# design.net
KiCad netlist of a schematic drawn in Altium Designer
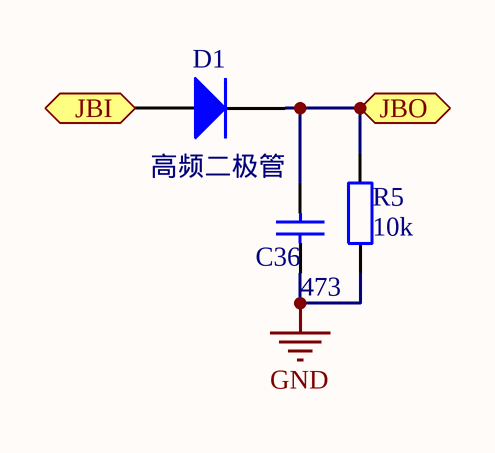
[diagram p0: 峰值检波.SchDoc]

(export (version "E")
  (design (tool "Eeschema 10.0.6"))
  (components
    (comp (ref "C36")
      (value "瓷片电容")
      (footprint "瓷片电容")
      (fields (field (name "ALTIUM_UNNAMED_1") "473"))
      (libsource (lib "自制库（原理图文件）") (part "瓷片电容"))
    )
    (comp (ref "D1")
      (value "高频二极管")
      (footprint "DO-41")
      (description "1 Amp General Purpose Rectifier")
      (fields (field (name "PUBLISHER") "Altium Limited"))
      (libsource (lib "Miscellaneous Devices") (part "Diode 1N4007"))
    )
    (comp (ref "R5")
      (value "10k")
      (footprint "AXIAL-0.4")
      (description "Resistor")
      (fields (field (name "Comment") "Res2") (field (name "PUBLISHER") "Altium Limited"))
      (libsource (lib "Miscellaneous Devices") (part "Res2"))
    )
  )
  (nets
    (net (code "1") (name "/JBI") (class "Default")
      (node (ref "D1") (pin "1") (pinfunction "A_1") (pintype "passive"))
    )
    (net (code "2") (name "/JBO") (class "Default")
      (node (ref "C36") (pin "2") (pinfunction "2_2") (pintype "passive"))
      (node (ref "D1") (pin "2") (pinfunction "K_2") (pintype "passive"))
      (node (ref "R5") (pin "2") (pinfunction "2_2") (pintype "passive"))
    )
    (net (code "3") (name "GND") (class "Default")
      (node (ref "C36") (pin "1") (pinfunction "1_1") (pintype "passive"))
      (node (ref "R5") (pin "1") (pinfunction "1_1") (pintype "passive"))
    )
  )
)
